# Gesamtschaltplan.net
KiCad netlist of a schematic drawn in EAGLE
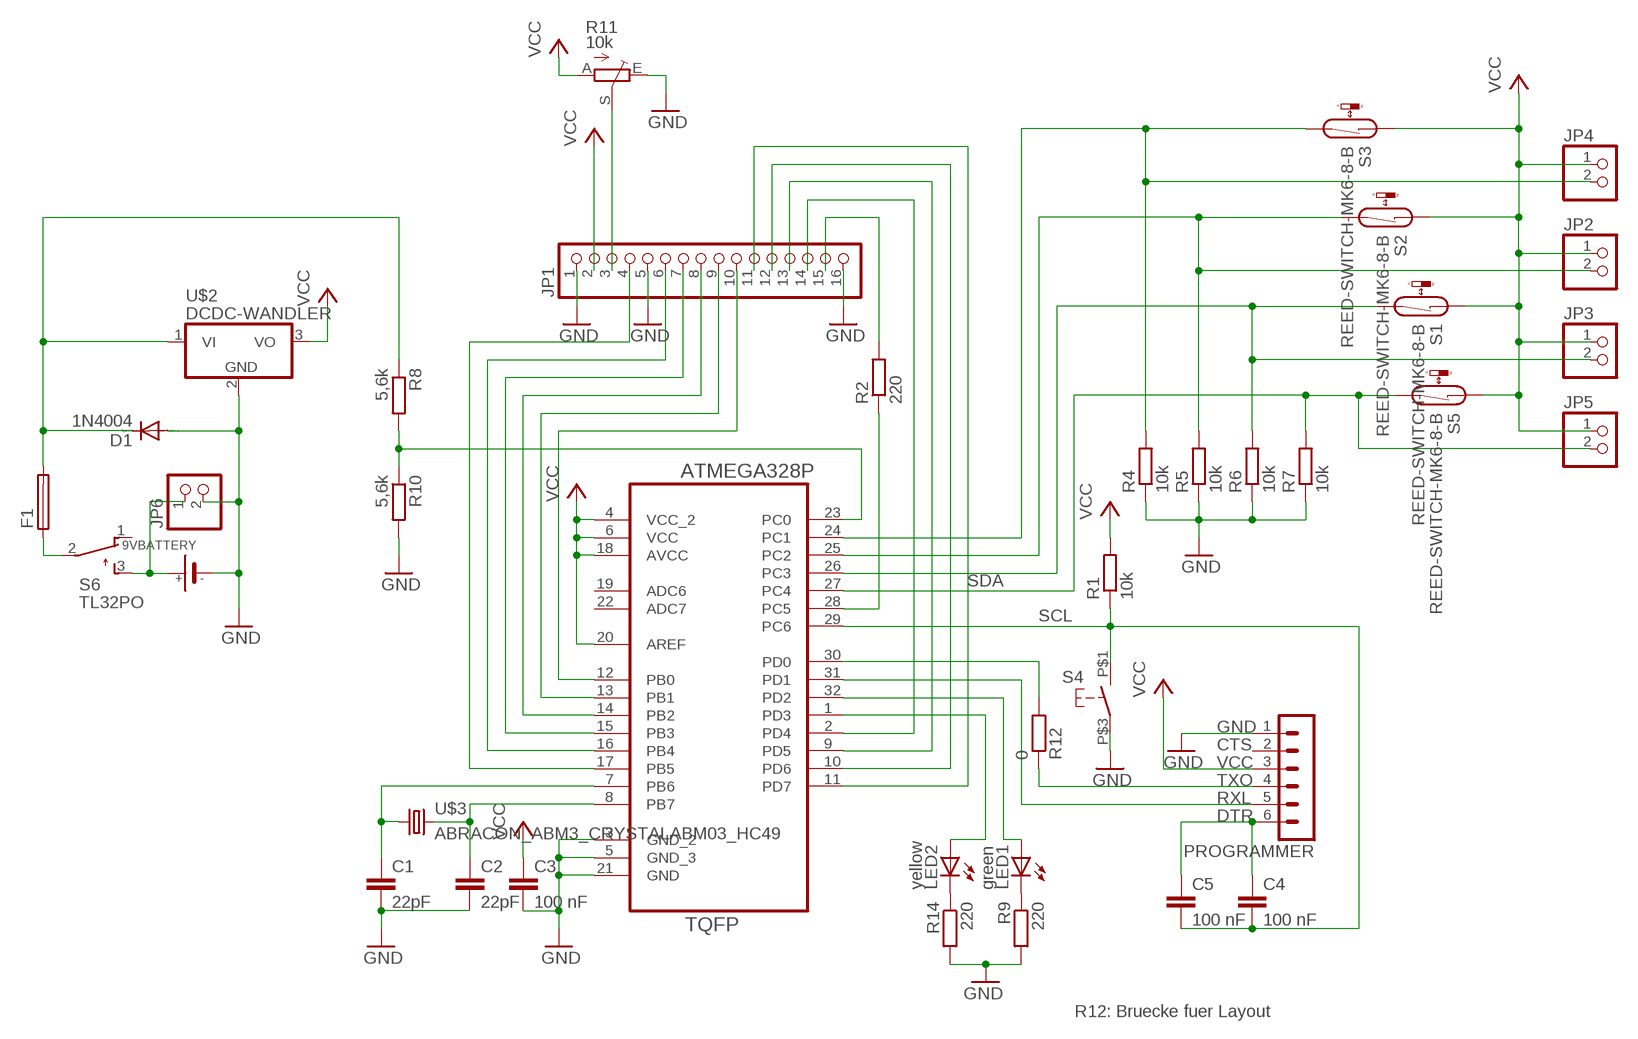
[diagram p0: schematic, sheet 1]

(export (version "E")
  (design (tool "Eeschema 10.0.6"))
  (components
    (comp (ref "C1")
      (value "22pF")
      (footprint "eagle-import:C0603K")
      (libsource (lib "eagle-import") (part "C-EUC0603K"))
    )
    (comp (ref "C2")
      (value "22pF")
      (footprint "eagle-import:C0603K")
      (libsource (lib "eagle-import") (part "C-EUC0603K"))
    )
    (comp (ref "C3")
      (value "100 nF")
      (footprint "eagle-import:C0603")
      (libsource (lib "eagle-import") (part "C-EUC0603"))
    )
    (comp (ref "C4")
      (value "100 nF")
      (footprint "eagle-import:C0603")
      (libsource (lib "eagle-import") (part "C-EUC0603"))
    )
    (comp (ref "C5")
      (value "100 nF")
      (footprint "eagle-import:C0603")
      (libsource (lib "eagle-import") (part "C-EUC0603"))
    )
    (comp (ref "D1")
      (value "1N4004")
      (footprint "eagle-import:DO41-10")
      (libsource (lib "eagle-import") (part "1N4004"))
    )
    (comp (ref "F1")
      (value "SH22,5A")
      (footprint "eagle-import:SH22,5A")
      (fields (field (name "MPN") "0031.7701.11"))
      (libsource (lib "eagle-import") (part "SH22,5A"))
    )
    (comp (ref "IC1")
      (value "ATMEGA328P-AU")
      (footprint "eagle-import:QFP80P900X900X120-32N")
      (libsource (lib "eagle-import") (part "ATMEGA328P-AU"))
    )
    (comp (ref "JP1")
      (value "PINHD-1X16")
      (footprint "eagle-import:1X16")
      (libsource (lib "eagle-import") (part "PINHD-1X16"))
    )
    (comp (ref "JP2")
      (value "PINHD-1X2")
      (footprint "eagle-import:1X02")
      (libsource (lib "eagle-import") (part "PINHD-1X2"))
    )
    (comp (ref "JP3")
      (value "PINHD-1X2")
      (footprint "eagle-import:1X02")
      (libsource (lib "eagle-import") (part "PINHD-1X2"))
    )
    (comp (ref "JP4")
      (value "PINHD-1X2")
      (footprint "eagle-import:1X02")
      (libsource (lib "eagle-import") (part "PINHD-1X2"))
    )
    (comp (ref "JP5")
      (value "PINHD-1X2")
      (footprint "eagle-import:1X02")
      (libsource (lib "eagle-import") (part "PINHD-1X2"))
    )
    (comp (ref "JP6")
      (value "PINHD-1X2")
      (footprint "eagle-import:1X02")
      (libsource (lib "eagle-import") (part "PINHD-1X2"))
    )
    (comp (ref "LED1")
      (value "green")
      (footprint "eagle-import:LED3MM")
      (libsource (lib "eagle-import") (part "LED3MM"))
    )
    (comp (ref "LED2")
      (value "yellow")
      (footprint "eagle-import:LED3MM")
      (libsource (lib "eagle-import") (part "LED3MM"))
    )
    (comp (ref "PROGRAMMER")
      (value "MA06-1")
      (footprint "eagle-import:MA06-1")
      (libsource (lib "eagle-import") (part "MA06-1"))
    )
    (comp (ref "R1")
      (value "10k")
      (footprint "eagle-import:R1206")
      (libsource (lib "eagle-import") (part "R-EU_R1206"))
    )
    (comp (ref "R2")
      (value "220")
      (footprint "eagle-import:R1206")
      (libsource (lib "eagle-import") (part "R-EU_R1206"))
    )
    (comp (ref "R4")
      (value "10k")
      (footprint "eagle-import:R1206")
      (libsource (lib "eagle-import") (part "R-EU_R1206"))
    )
    (comp (ref "R5")
      (value "10k")
      (footprint "eagle-import:R1206")
      (libsource (lib "eagle-import") (part "R-EU_R1206"))
    )
    (comp (ref "R6")
      (value "10k")
      (footprint "eagle-import:R1206")
      (libsource (lib "eagle-import") (part "R-EU_R1206"))
    )
    (comp (ref "R7")
      (value "10k")
      (footprint "eagle-import:R1206")
      (libsource (lib "eagle-import") (part "R-EU_R1206"))
    )
    (comp (ref "R8")
      (value "5,6k")
      (footprint "eagle-import:R1206")
      (libsource (lib "eagle-import") (part "R-EU_R1206"))
    )
    (comp (ref "R9")
      (value "220")
      (footprint "eagle-import:R1206")
      (libsource (lib "eagle-import") (part "R-EU_R1206"))
    )
    (comp (ref "R10")
      (value "5,6k")
      (footprint "eagle-import:R1206")
      (libsource (lib "eagle-import") (part "R-EU_R1206"))
    )
    (comp (ref "R11")
      (value "10k")
      (footprint "eagle-import:PT-10")
      (libsource (lib "eagle-import") (part "TRIM_EU-PT10"))
    )
    (comp (ref "R12")
      (value "0")
      (footprint "eagle-import:R1206")
      (libsource (lib "eagle-import") (part "R-EU_R1206"))
    )
    (comp (ref "R14")
      (value "220")
      (footprint "eagle-import:R1206")
      (libsource (lib "eagle-import") (part "R-EU_R1206"))
    )
    (comp (ref "S1")
      (value "REED-SWITCH-MK6-8-B")
      (footprint "eagle-import:MK6-8-A")
      (fields (field (name "MF") "MEDER") (field (name "MPN") "MK6-8-B"))
      (libsource (lib "eagle-import") (part "REED-SWITCH-MK6-8-B"))
    )
    (comp (ref "S2")
      (value "REED-SWITCH-MK6-8-B")
      (footprint "eagle-import:MK6-8-A")
      (fields (field (name "MF") "MEDER") (field (name "MPN") "MK6-8-B"))
      (libsource (lib "eagle-import") (part "REED-SWITCH-MK6-8-B"))
    )
    (comp (ref "S3")
      (value "REED-SWITCH-MK6-8-B")
      (footprint "eagle-import:MK6-8-A")
      (fields (field (name "MF") "MEDER") (field (name "MPN") "MK6-8-B"))
      (libsource (lib "eagle-import") (part "REED-SWITCH-MK6-8-B"))
    )
    (comp (ref "S4")
      (value "SCHLIESSER_TASTSCHALTER")
      (footprint "eagle-import:NAMAE-JTP-1130")
      (libsource (lib "eagle-import") (part "SCHLIESSER_TASTSCHALTER"))
    )
    (comp (ref "S5")
      (value "REED-SWITCH-MK6-8-B")
      (footprint "eagle-import:MK6-8-A")
      (fields (field (name "MF") "MEDER") (field (name "MPN") "MK6-8-B"))
      (libsource (lib "eagle-import") (part "REED-SWITCH-MK6-8-B"))
    )
    (comp (ref "S6")
      (value "TL32PO")
      (footprint "eagle-import:TL3XPO")
      (libsource (lib "eagle-import") (part "TL32PO"))
    )
    (comp (ref "U$1")
      (value "9VBATTERY")
      (footprint "eagle-import:BATTERIEHALTER-54X30")
      (libsource (lib "eagle-import") (part "9VBATTERY"))
    )
    (comp (ref "U$2")
      (value "DCDC-WANDLER")
      (footprint "eagle-import:TRACOPOWER-DCDCWANDER-TSR1")
      (libsource (lib "eagle-import") (part "DCDC-WANDLER"))
    )
    (comp (ref "U$3")
      (value "ABRACON_ABM3_CRYSTALABM03_HC49")
      (footprint "eagle-import:ABM03_HC49")
      (libsource (lib "eagle-import") (part "ABRACON_ABM3_CRYSTALABM03_HC49"))
    )
  )
  (nets
    (net (code "1") (name "GND") (class "Default")
      (node (ref "C1") (pin "2") (pinfunction "2_2") (pintype "passive"))
      (node (ref "C2") (pin "2") (pinfunction "2_2") (pintype "passive"))
      (node (ref "C3") (pin "2") (pinfunction "2_2") (pintype "passive"))
      (node (ref "D1") (pin "A") (pinfunction "A_A") (pintype "passive"))
      (node (ref "IC1") (pin "21") (pinfunction "GND_21") (pintype "passive"))
      (node (ref "IC1") (pin "3") (pinfunction "GND_2_3") (pintype "passive"))
      (node (ref "IC1") (pin "5") (pinfunction "GND_3_5") (pintype "passive"))
      (node (ref "JP1") (pin "1") (pinfunction "1_1") (pintype "passive"))
      (node (ref "JP1") (pin "16") (pinfunction "16_16") (pintype "passive"))
      (node (ref "JP1") (pin "5") (pinfunction "5_5") (pintype "passive"))
      (node (ref "JP6") (pin "2") (pinfunction "2_2") (pintype "passive"))
      (node (ref "PROGRAMMER") (pin "1") (pinfunction "1_1") (pintype "passive"))
      (node (ref "R10") (pin "2") (pinfunction "2_2") (pintype "passive"))
      (node (ref "R11") (pin "E") (pinfunction "E_E") (pintype "passive"))
      (node (ref "R14") (pin "2") (pinfunction "2_2") (pintype "passive"))
      (node (ref "R4") (pin "1") (pinfunction "1_1") (pintype "passive"))
      (node (ref "R5") (pin "1") (pinfunction "1_1") (pintype "passive"))
      (node (ref "R6") (pin "1") (pinfunction "1_1") (pintype "passive"))
      (node (ref "R7") (pin "1") (pinfunction "1_1") (pintype "passive"))
      (node (ref "R9") (pin "2") (pinfunction "2_2") (pintype "passive"))
      (node (ref "S4") (pin "P$3") (pinfunction "4_P$3") (pintype "input"))
      (node (ref "U$1") (pin "P$2") (pinfunction "P$2_P$2") (pintype "bidirectional"))
      (node (ref "U$2") (pin "2") (pinfunction "GND_2") (pintype "passive"))
    )
    (net (code "2") (name "Net-(C4-Pad1)") (class "Default")
      (node (ref "C4") (pin "1") (pinfunction "1_1") (pintype "passive"))
      (node (ref "C5") (pin "1") (pinfunction "1_1") (pintype "passive"))
      (node (ref "PROGRAMMER") (pin "6") (pinfunction "6_6") (pintype "passive"))
    )
    (net (code "3") (name "Net-(IC1-PB0)") (class "Default")
      (node (ref "IC1") (pin "12") (pinfunction "PB0_12") (pintype "bidirectional"))
      (node (ref "JP1") (pin "10") (pinfunction "10_10") (pintype "passive"))
    )
    (net (code "4") (name "Net-(IC1-PB1)") (class "Default")
      (node (ref "IC1") (pin "13") (pinfunction "PB1_13") (pintype "bidirectional"))
      (node (ref "JP1") (pin "9") (pinfunction "9_9") (pintype "passive"))
    )
    (net (code "5") (name "Net-(IC1-PB2)") (class "Default")
      (node (ref "IC1") (pin "14") (pinfunction "PB2_14") (pintype "bidirectional"))
      (node (ref "JP1") (pin "8") (pinfunction "8_8") (pintype "passive"))
    )
    (net (code "6") (name "Net-(IC1-PB3)") (class "Default")
      (node (ref "IC1") (pin "15") (pinfunction "PB3_15") (pintype "bidirectional"))
      (node (ref "JP1") (pin "7") (pinfunction "7_7") (pintype "passive"))
    )
    (net (code "7") (name "Net-(IC1-PB4)") (class "Default")
      (node (ref "IC1") (pin "16") (pinfunction "PB4_16") (pintype "bidirectional"))
      (node (ref "JP1") (pin "6") (pinfunction "6_6") (pintype "passive"))
    )
    (net (code "8") (name "Net-(IC1-PB5)") (class "Default")
      (node (ref "IC1") (pin "17") (pinfunction "PB5_17") (pintype "bidirectional"))
      (node (ref "JP1") (pin "4") (pinfunction "4_4") (pintype "passive"))
    )
    (net (code "9") (name "Net-(IC1-PB6)") (class "Default")
      (node (ref "C1") (pin "1") (pinfunction "1_1") (pintype "passive"))
      (node (ref "IC1") (pin "7") (pinfunction "PB6_7") (pintype "bidirectional"))
      (node (ref "U$3") (pin "1") (pinfunction "1_1") (pintype "passive"))
    )
    (net (code "10") (name "Net-(IC1-PB7)") (class "Default")
      (node (ref "C2") (pin "1") (pinfunction "1_1") (pintype "passive"))
      (node (ref "IC1") (pin "8") (pinfunction "PB7_8") (pintype "bidirectional"))
      (node (ref "U$3") (pin "2") (pinfunction "2_2") (pintype "passive"))
    )
    (net (code "11") (name "Net-(IC1-PC0)") (class "Default")
      (node (ref "IC1") (pin "23") (pinfunction "PC0_23") (pintype "bidirectional"))
      (node (ref "R10") (pin "1") (pinfunction "1_1") (pintype "passive"))
      (node (ref "R8") (pin "2") (pinfunction "2_2") (pintype "passive"))
    )
    (net (code "12") (name "Net-(IC1-PC1)") (class "Default")
      (node (ref "IC1") (pin "24") (pinfunction "PC1_24") (pintype "bidirectional"))
      (node (ref "JP4") (pin "2") (pinfunction "2_2") (pintype "passive"))
      (node (ref "R4") (pin "2") (pinfunction "2_2") (pintype "passive"))
      (node (ref "S3") (pin "2") (pinfunction "2_2") (pintype "passive"))
    )
    (net (code "13") (name "Net-(IC1-PC2)") (class "Default")
      (node (ref "IC1") (pin "25") (pinfunction "PC2_25") (pintype "bidirectional"))
      (node (ref "JP2") (pin "2") (pinfunction "2_2") (pintype "passive"))
      (node (ref "R5") (pin "2") (pinfunction "2_2") (pintype "passive"))
      (node (ref "S2") (pin "2") (pinfunction "2_2") (pintype "passive"))
    )
    (net (code "14") (name "Net-(IC1-PC3)") (class "Default")
      (node (ref "IC1") (pin "26") (pinfunction "PC3_26") (pintype "bidirectional"))
      (node (ref "JP3") (pin "2") (pinfunction "2_2") (pintype "passive"))
      (node (ref "R6") (pin "2") (pinfunction "2_2") (pintype "passive"))
      (node (ref "S1") (pin "2") (pinfunction "2_2") (pintype "passive"))
    )
    (net (code "15") (name "Net-(IC1-PC4)") (class "Default")
      (node (ref "IC1") (pin "27") (pinfunction "PC4_27") (pintype "bidirectional"))
      (node (ref "JP5") (pin "2") (pinfunction "2_2") (pintype "passive"))
      (node (ref "R7") (pin "2") (pinfunction "2_2") (pintype "passive"))
      (node (ref "S5") (pin "2") (pinfunction "2_2") (pintype "passive"))
    )
    (net (code "16") (name "Net-(IC1-PC5)") (class "Default")
      (node (ref "IC1") (pin "28") (pinfunction "PC5_28") (pintype "bidirectional"))
      (node (ref "R2") (pin "1") (pinfunction "1_1") (pintype "passive"))
    )
    (net (code "17") (name "Net-(IC1-PC6)") (class "Default")
      (node (ref "C4") (pin "2") (pinfunction "2_2") (pintype "passive"))
      (node (ref "C5") (pin "2") (pinfunction "2_2") (pintype "passive"))
      (node (ref "IC1") (pin "29") (pinfunction "PC6_29") (pintype "bidirectional"))
      (node (ref "R1") (pin "1") (pinfunction "1_1") (pintype "passive"))
      (node (ref "S4") (pin "P$1") (pinfunction "3_P$1") (pintype "input"))
    )
    (net (code "18") (name "Net-(IC1-PD0)") (class "Default")
      (node (ref "IC1") (pin "30") (pinfunction "PD0_30") (pintype "bidirectional"))
      (node (ref "R12") (pin "2") (pinfunction "2_2") (pintype "passive"))
    )
    (net (code "19") (name "Net-(IC1-PD1)") (class "Default")
      (node (ref "IC1") (pin "31") (pinfunction "PD1_31") (pintype "bidirectional"))
      (node (ref "PROGRAMMER") (pin "5") (pinfunction "5_5") (pintype "passive"))
    )
    (net (code "20") (name "Net-(IC1-PD2)") (class "Default")
      (node (ref "IC1") (pin "32") (pinfunction "PD2_32") (pintype "bidirectional"))
      (node (ref "LED1") (pin "A") (pinfunction "A_A") (pintype "passive"))
    )
    (net (code "21") (name "Net-(IC1-PD3)") (class "Default")
      (node (ref "IC1") (pin "1") (pinfunction "PD3_1") (pintype "bidirectional"))
      (node (ref "LED2") (pin "A") (pinfunction "A_A") (pintype "passive"))
    )
    (net (code "22") (name "Net-(IC1-PD4)") (class "Default")
      (node (ref "IC1") (pin "2") (pinfunction "PD4_2") (pintype "bidirectional"))
      (node (ref "JP1") (pin "14") (pinfunction "14_14") (pintype "passive"))
    )
    (net (code "23") (name "Net-(IC1-PD5)") (class "Default")
      (node (ref "IC1") (pin "9") (pinfunction "PD5_9") (pintype "bidirectional"))
      (node (ref "JP1") (pin "13") (pinfunction "13_13") (pintype "passive"))
    )
    (net (code "24") (name "Net-(IC1-PD6)") (class "Default")
      (node (ref "IC1") (pin "10") (pinfunction "PD6_10") (pintype "bidirectional"))
      (node (ref "JP1") (pin "12") (pinfunction "12_12") (pintype "passive"))
    )
    (net (code "25") (name "Net-(IC1-PD7)") (class "Default")
      (node (ref "IC1") (pin "11") (pinfunction "PD7_11") (pintype "bidirectional"))
      (node (ref "JP1") (pin "11") (pinfunction "11_11") (pintype "passive"))
    )
    (net (code "26") (name "Net-(JP1-Pad3)") (class "Default")
      (node (ref "JP1") (pin "3") (pinfunction "3_3") (pintype "passive"))
      (node (ref "R11") (pin "S") (pinfunction "S_S") (pintype "passive"))
    )
    (net (code "27") (name "Net-(JP1-Pad15)") (class "Default")
      (node (ref "JP1") (pin "15") (pinfunction "15_15") (pintype "passive"))
      (node (ref "R2") (pin "2") (pinfunction "2_2") (pintype "passive"))
    )
    (net (code "28") (name "Net-(LED1-C)") (class "Default")
      (node (ref "LED1") (pin "K") (pinfunction "C_K") (pintype "passive"))
      (node (ref "R9") (pin "1") (pinfunction "1_1") (pintype "passive"))
    )
    (net (code "29") (name "Net-(LED2-C)") (class "Default")
      (node (ref "LED2") (pin "K") (pinfunction "C_K") (pintype "passive"))
      (node (ref "R14") (pin "1") (pinfunction "1_1") (pintype "passive"))
    )
    (net (code "30") (name "Net-(PROGRAMMER-Pad4)") (class "Default")
      (node (ref "PROGRAMMER") (pin "4") (pinfunction "4_4") (pintype "passive"))
      (node (ref "R12") (pin "1") (pinfunction "1_1") (pintype "passive"))
    )
    (net (code "31") (name "Net-(S6-P)") (class "Default")
      (node (ref "F1") (pin "1") (pinfunction "1_1") (pintype "passive"))
      (node (ref "S6") (pin "2") (pinfunction "P_2") (pintype "passive"))
    )
    (net (code "32") (name "Net-(S6-S)") (class "Default")
      (node (ref "JP6") (pin "1") (pinfunction "1_1") (pintype "passive"))
      (node (ref "S6") (pin "3") (pinfunction "S_3") (pintype "passive"))
      (node (ref "U$1") (pin "P$1") (pinfunction "P$1_P$1") (pintype "bidirectional"))
    )
    (net (code "33") (name "Net-(U$2-VI)") (class "Default")
      (node (ref "D1") (pin "C") (pinfunction "C_C") (pintype "passive"))
      (node (ref "F1") (pin "2") (pinfunction "2_2") (pintype "passive"))
      (node (ref "R8") (pin "1") (pinfunction "1_1") (pintype "passive"))
      (node (ref "U$2") (pin "1") (pinfunction "VI_1") (pintype "input"))
    )
    (net (code "34") (name "VCC") (class "Default")
      (node (ref "C3") (pin "1") (pinfunction "1_1") (pintype "passive"))
      (node (ref "IC1") (pin "18") (pinfunction "AVCC_18") (pintype "power_in"))
      (node (ref "IC1") (pin "20") (pinfunction "AREF_20") (pintype "input"))
      (node (ref "IC1") (pin "4") (pinfunction "VCC_2_4") (pintype "power_in"))
      (node (ref "IC1") (pin "6") (pinfunction "VCC_6") (pintype "power_in"))
      (node (ref "JP1") (pin "2") (pinfunction "2_2") (pintype "passive"))
      (node (ref "JP2") (pin "1") (pinfunction "1_1") (pintype "passive"))
      (node (ref "JP3") (pin "1") (pinfunction "1_1") (pintype "passive"))
      (node (ref "JP4") (pin "1") (pinfunction "1_1") (pintype "passive"))
      (node (ref "JP5") (pin "1") (pinfunction "1_1") (pintype "passive"))
      (node (ref "PROGRAMMER") (pin "3") (pinfunction "3_3") (pintype "passive"))
      (node (ref "R1") (pin "2") (pinfunction "2_2") (pintype "passive"))
      (node (ref "R11") (pin "A") (pinfunction "A_A") (pintype "passive"))
      (node (ref "S1") (pin "1") (pinfunction "1_1") (pintype "passive"))
      (node (ref "S2") (pin "1") (pinfunction "1_1") (pintype "passive"))
      (node (ref "S3") (pin "1") (pinfunction "1_1") (pintype "passive"))
      (node (ref "S5") (pin "1") (pinfunction "1_1") (pintype "passive"))
      (node (ref "U$2") (pin "3") (pinfunction "VO_3") (pintype "passive"))
    )
    (net (code "35") (name "unconnected-(IC1-ADC6-Pad19)") (class "Default")
      (node (ref "IC1") (pin "19") (pinfunction "ADC6_19") (pintype "input"))
    )
    (net (code "36") (name "unconnected-(IC1-ADC7-Pad22)") (class "Default")
      (node (ref "IC1") (pin "22") (pinfunction "ADC7_22") (pintype "input"))
    )
    (net (code "37") (name "unconnected-(PROGRAMMER-Pad2)") (class "Default")
      (node (ref "PROGRAMMER") (pin "2") (pinfunction "2_2") (pintype "passive"))
    )
    (net (code "38") (name "unconnected-(S6-O-Pad1)") (class "Default")
      (node (ref "S6") (pin "1") (pinfunction "O_1") (pintype "passive"))
    )
  )
)
